# storage.net
KiCad netlist of a schematic drawn in Altium Designer
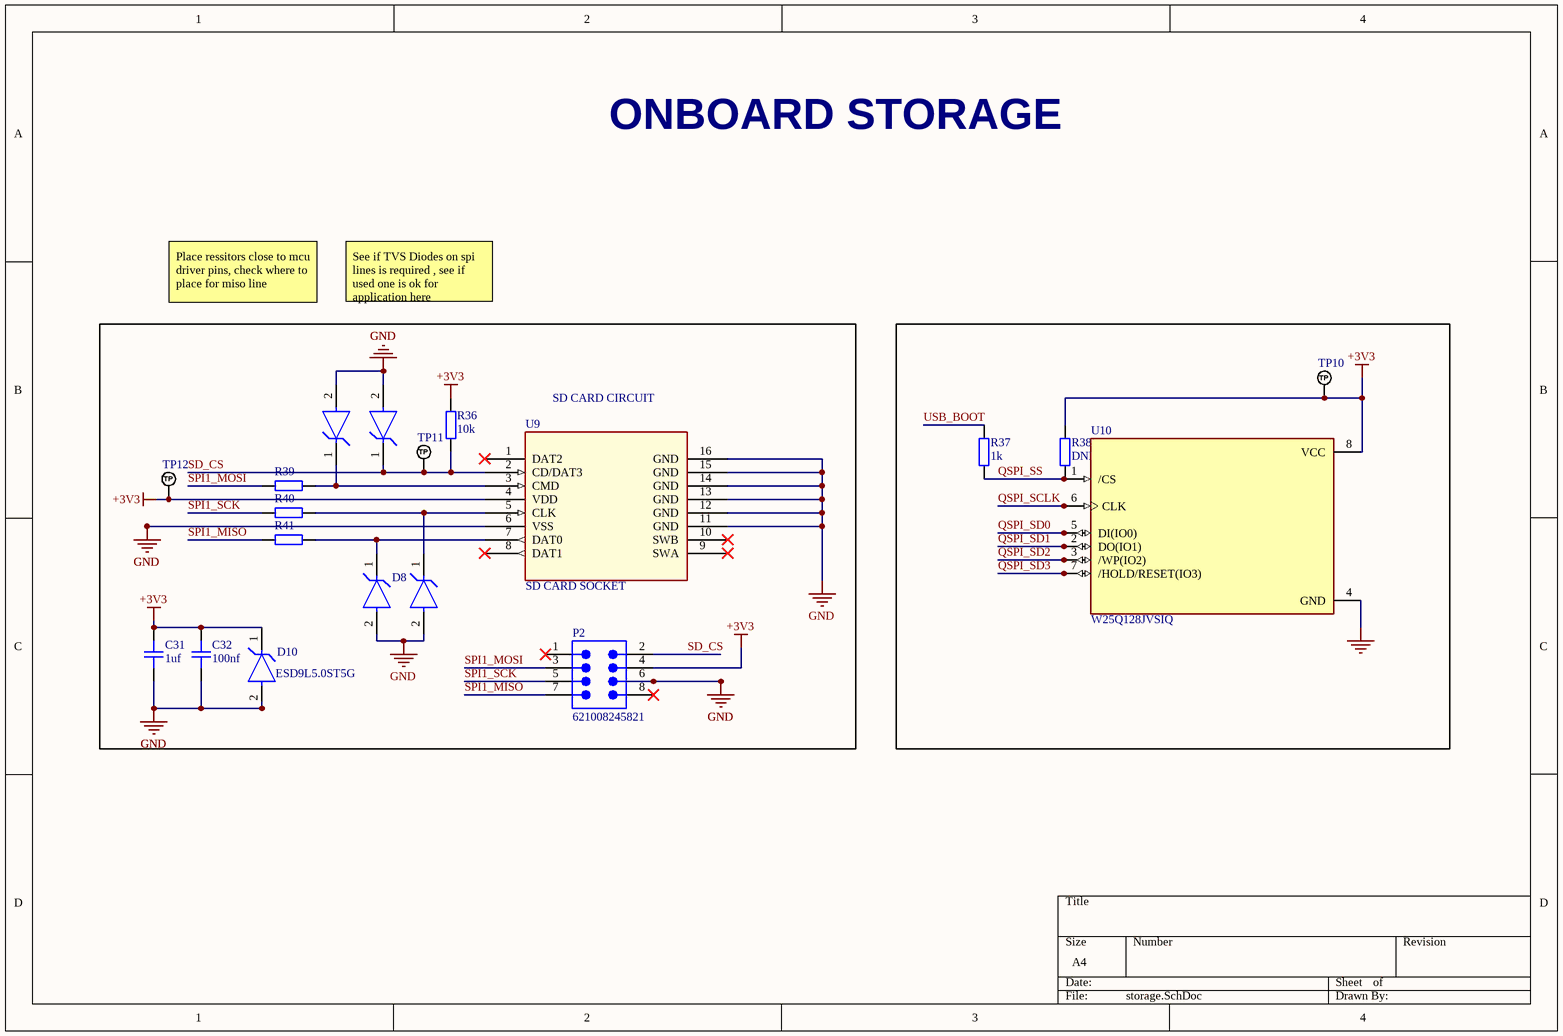
[diagram p0: storage.SchDoc]

(export (version "E")
  (design (tool "Eeschema 10.0.6"))
  (components
    (comp (ref "C31")
      (value "1uf")
      (footprint "CAP_0805")
      (description "Capacitor SMD 0805")
      (libsource (lib "SchematicSchlib1") (part "CAP_0805"))
    )
    (comp (ref "C32")
      (value "100nf")
      (footprint "CAP_0402")
      (description "Capacitor SMD 0402")
      (libsource (lib "SchematicSchlib1") (part "CAP_0402"))
    )
    (comp (ref "D6")
      (value "ESD9L5.0ST5G")
      (footprint "On_Semiconductor_514AB_MFG")
      (libsource (lib "Altium Content Vault") (part "ESD9L5_0ST5G"))
    )
    (comp (ref "D7")
      (value "ESD9L5.0ST5G")
      (footprint "On_Semiconductor_514AB_MFG")
      (libsource (lib "Altium Content Vault") (part "ESD9L5_0ST5G"))
    )
    (comp (ref "D8")
      (value "ESD9L5.0ST5G")
      (footprint "On_Semiconductor_514AB_MFG")
      (libsource (lib "Altium Content Vault") (part "ESD9L5_0ST5G"))
    )
    (comp (ref "D9")
      (value "ESD9L5.0ST5G")
      (footprint "On_Semiconductor_514AB_MFG")
      (libsource (lib "Altium Content Vault") (part "ESD9L5_0ST5G"))
    )
    (comp (ref "D10")
      (value "ESD9L5.0ST5G")
      (footprint "On_Semiconductor_514AB_MFG")
      (libsource (lib "Altium Content Vault") (part "ESD9L5_0ST5G"))
    )
    (comp (ref "P2")
      (value "621008245821")
      (footprint "621008245821")
      (description "SMT Vertical Pin Header WR-PHD, Pitch 2.00 mm, Dual Row, 8 pins")
      (libsource (lib "Altium Content Vault") (part "Header_Male_2R_08P"))
    )
    (comp (ref "R36")
      (value "10k")
      (footprint "RES_0603")
      (description "Resistor SMD 0603")
      (libsource (lib "SchematicSchlib1") (part "RES_0603"))
    )
    (comp (ref "R37")
      (value "1k")
      (footprint "RES_0402")
      (description "Resistor SMD 0402")
      (libsource (lib "SchematicSchlib1") (part "RES_0402"))
    )
    (comp (ref "R38")
      (value "DNF")
      (footprint "RES_0402")
      (description "Resistor SMD 0402")
      (libsource (lib "SchematicSchlib1") (part "RES_0402"))
    )
    (comp (ref "R39")
      (value "22 ohm")
      (footprint "RES_0603")
      (description "Resistor SMD 0603")
      (libsource (lib "SchematicSchlib1") (part "RES_0603"))
    )
    (comp (ref "R40")
      (value "22 ohm")
      (footprint "RES_0603")
      (description "Resistor SMD 0603")
      (libsource (lib "SchematicSchlib1") (part "RES_0603"))
    )
    (comp (ref "R41")
      (value "22 ohm")
      (footprint "RES_0603")
      (description "Resistor SMD 0603")
      (libsource (lib "SchematicSchlib1") (part "RES_0603"))
    )
    (comp (ref "TP10")
      (value "TEST_POINT_RND_1MM")
      (footprint "PAD_RND_1MM")
      (description "Test Point Round 1mm (NO BOM)")
      (fields (field (name "SOURCE") "Schematic-Lib-PhilsLab.SchLib"))
      (libsource (lib "Shravan Talapady") (part "TEST_POINT_RND_1MM"))
    )
    (comp (ref "TP11")
      (value "TEST_POINT_RND_1MM")
      (footprint "PAD_RND_1MM")
      (description "Test Point Round 1mm (NO BOM)")
      (fields (field (name "SOURCE") "Schematic-Lib-PhilsLab.SchLib"))
      (libsource (lib "Shravan Talapady") (part "TEST_POINT_RND_1MM"))
    )
    (comp (ref "TP12")
      (value "TEST_POINT_RND_1MM")
      (footprint "PAD_RND_1MM")
      (description "Test Point Round 1mm (NO BOM)")
      (fields (field (name "SOURCE") "Schematic-Lib-PhilsLab.SchLib"))
      (libsource (lib "Shravan Talapady") (part "TEST_POINT_RND_1MM"))
    )
    (comp (ref "U9")
      (value "SD CARD SOCKET")
      (footprint "SD CARD SOCKET")
      (libsource (lib "SchematicSchlib1") (part "SD CARD SOCKET"))
    )
    (comp (ref "U10")
      (value "W25Q128JVSIQ")
      (footprint "SOIC127P790X216-8N")
      (description "FLASH - NOR Memory IC 128Mb (16M x 8) SPI - Quad I/O, QPI, DTR 133 MHz 8-SOIC")
      (fields (field (name "MF") "Winbond Electronics"))
      (libsource (lib "SchematicSchlib1") (part "W25Q128JVSIQ"))
    )
  )
  (nets
    (net (code "1") (name "+3V3") (class "Default")
      (node (ref "C31") (pin "2") (pinfunction "2_2") (pintype "passive"))
      (node (ref "C32") (pin "2") (pinfunction "2_2") (pintype "passive"))
      (node (ref "D10") (pin "1") (pinfunction "C_1") (pintype "passive"))
      (node (ref "P2") (pin "4") (pinfunction "4_4") (pintype "passive"))
      (node (ref "R36") (pin "2") (pinfunction "2_2") (pintype "passive"))
      (node (ref "R38") (pin "2") (pinfunction "2_2") (pintype "passive"))
      (node (ref "TP10") (pin "1") (pinfunction "TP_1") (pintype "passive"))
      (node (ref "TP12") (pin "1") (pinfunction "TP_1") (pintype "passive"))
      (node (ref "U10") (pin "8") (pinfunction "VCC_8") (pintype "power_in"))
      (node (ref "U9") (pin "4") (pinfunction "VDD_4") (pintype "power_in"))
    )
    (net (code "3") (name "/QSPI_SCLK") (class "Default")
      (node (ref "U10") (pin "6") (pinfunction "CLK_6") (pintype "input"))
    )
    (net (code "4") (name "/QSPI_SD0") (class "Default")
      (node (ref "U10") (pin "5") (pinfunction "DI(IO0)_5") (pintype "bidirectional"))
    )
    (net (code "5") (name "/QSPI_SD1") (class "Default")
      (node (ref "U10") (pin "2") (pinfunction "DO(IO1)_2") (pintype "bidirectional"))
    )
    (net (code "6") (name "/QSPI_SD2") (class "Default")
      (node (ref "U10") (pin "3") (pinfunction "/WP(IO2)_3") (pintype "bidirectional"))
    )
    (net (code "7") (name "/QSPI_SD3") (class "Default")
      (node (ref "U10") (pin "7") (pinfunction "/HOLD/RESET(IO3)_7") (pintype "bidirectional"))
    )
    (net (code "8") (name "/QSPI_SS") (class "Default")
      (node (ref "R37") (pin "1") (pinfunction "1_1") (pintype "passive"))
      (node (ref "R38") (pin "1") (pinfunction "1_1") (pintype "passive"))
      (node (ref "U10") (pin "1") (pinfunction "/CS_1") (pintype "input"))
    )
    (net (code "9") (name "/SD_CS") (class "Default")
      (node (ref "D7") (pin "1") (pinfunction "C_1") (pintype "passive"))
      (node (ref "P2") (pin "2") (pinfunction "2_2") (pintype "passive"))
      (node (ref "R36") (pin "1") (pinfunction "1_1") (pintype "passive"))
      (node (ref "TP11") (pin "1") (pinfunction "TP_1") (pintype "passive"))
      (node (ref "U9") (pin "2") (pinfunction "CD/DAT3_2") (pintype "input"))
    )
    (net (code "10") (name "/SPI1_MISO") (class "Default")
      (node (ref "P2") (pin "7") (pinfunction "7_7") (pintype "passive"))
      (node (ref "R41") (pin "1") (pinfunction "1_1") (pintype "passive"))
    )
    (net (code "11") (name "/SPI1_MOSI") (class "Default")
      (node (ref "P2") (pin "3") (pinfunction "3_3") (pintype "passive"))
      (node (ref "R39") (pin "1") (pinfunction "1_1") (pintype "passive"))
    )
    (net (code "12") (name "/SPI1_SCK") (class "Default")
      (node (ref "P2") (pin "5") (pinfunction "5_5") (pintype "passive"))
      (node (ref "R40") (pin "1") (pinfunction "1_1") (pintype "passive"))
    )
    (net (code "13") (name "/USB_BOOT") (class "Default")
      (node (ref "R37") (pin "2") (pinfunction "2_2") (pintype "passive"))
    )
    (net (code "14") (name "GND") (class "Default")
      (node (ref "C31") (pin "1") (pinfunction "1_1") (pintype "passive"))
      (node (ref "C32") (pin "1") (pinfunction "1_1") (pintype "passive"))
      (node (ref "D10") (pin "2") (pinfunction "A_2") (pintype "passive"))
      (node (ref "D6") (pin "2") (pinfunction "A_2") (pintype "passive"))
      (node (ref "D7") (pin "2") (pinfunction "A_2") (pintype "passive"))
      (node (ref "D8") (pin "2") (pinfunction "A_2") (pintype "passive"))
      (node (ref "D9") (pin "2") (pinfunction "A_2") (pintype "passive"))
      (node (ref "P2") (pin "6") (pinfunction "6_6") (pintype "passive"))
      (node (ref "U10") (pin "4") (pinfunction "GND_4") (pintype "power_in"))
      (node (ref "U9") (pin "11") (pinfunction "GND_11") (pintype "power_in"))
      (node (ref "U9") (pin "12") (pinfunction "GND_12") (pintype "power_in"))
      (node (ref "U9") (pin "13") (pinfunction "GND_13") (pintype "power_in"))
      (node (ref "U9") (pin "14") (pinfunction "GND_14") (pintype "power_in"))
      (node (ref "U9") (pin "15") (pinfunction "GND_15") (pintype "power_in"))
      (node (ref "U9") (pin "16") (pinfunction "GND_16") (pintype "power_in"))
      (node (ref "U9") (pin "6") (pinfunction "VSS_6") (pintype "power_in"))
    )
    (net (code "15") (name "Net-(D6-C)") (class "Default")
      (node (ref "D6") (pin "1") (pinfunction "C_1") (pintype "passive"))
      (node (ref "R39") (pin "2") (pinfunction "2_2") (pintype "passive"))
      (node (ref "U9") (pin "3") (pinfunction "CMD_3") (pintype "input"))
    )
    (net (code "16") (name "Net-(D8-C)") (class "Default")
      (node (ref "D8") (pin "1") (pinfunction "C_1") (pintype "passive"))
      (node (ref "R41") (pin "2") (pinfunction "2_2") (pintype "passive"))
      (node (ref "U9") (pin "7") (pinfunction "DAT0_7") (pintype "output"))
    )
    (net (code "17") (name "Net-(D9-C)") (class "Default")
      (node (ref "D9") (pin "1") (pinfunction "C_1") (pintype "passive"))
      (node (ref "R40") (pin "2") (pinfunction "2_2") (pintype "passive"))
      (node (ref "U9") (pin "5") (pinfunction "CLK_5") (pintype "input"))
    )
    (net (code "18") (name "unconnected-(P2-Pad1)") (class "Default")
      (node (ref "P2") (pin "1") (pinfunction "1_1") (pintype "passive+no_connect"))
    )
    (net (code "19") (name "unconnected-(P2-Pad8)") (class "Default")
      (node (ref "P2") (pin "8") (pinfunction "8_8") (pintype "passive+no_connect"))
    )
    (net (code "20") (name "unconnected-(U9-DAT1-Pad8)") (class "Default")
      (node (ref "U9") (pin "8") (pinfunction "DAT1_8") (pintype "output+no_connect"))
    )
    (net (code "21") (name "unconnected-(U9-DAT2-Pad1)") (class "Default")
      (node (ref "U9") (pin "1") (pinfunction "DAT2_1") (pintype "passive+no_connect"))
    )
    (net (code "22") (name "unconnected-(U9-SWA-Pad9)") (class "Default")
      (node (ref "U9") (pin "9") (pinfunction "SWA_9") (pintype "passive+no_connect"))
    )
    (net (code "23") (name "unconnected-(U9-SWB-Pad10)") (class "Default")
      (node (ref "U9") (pin "10") (pinfunction "SWB_10") (pintype "passive+no_connect"))
    )
  )
)
